# 16_PWM_LEDs_Module.net
KiCad netlist of a schematic drawn in EAGLE
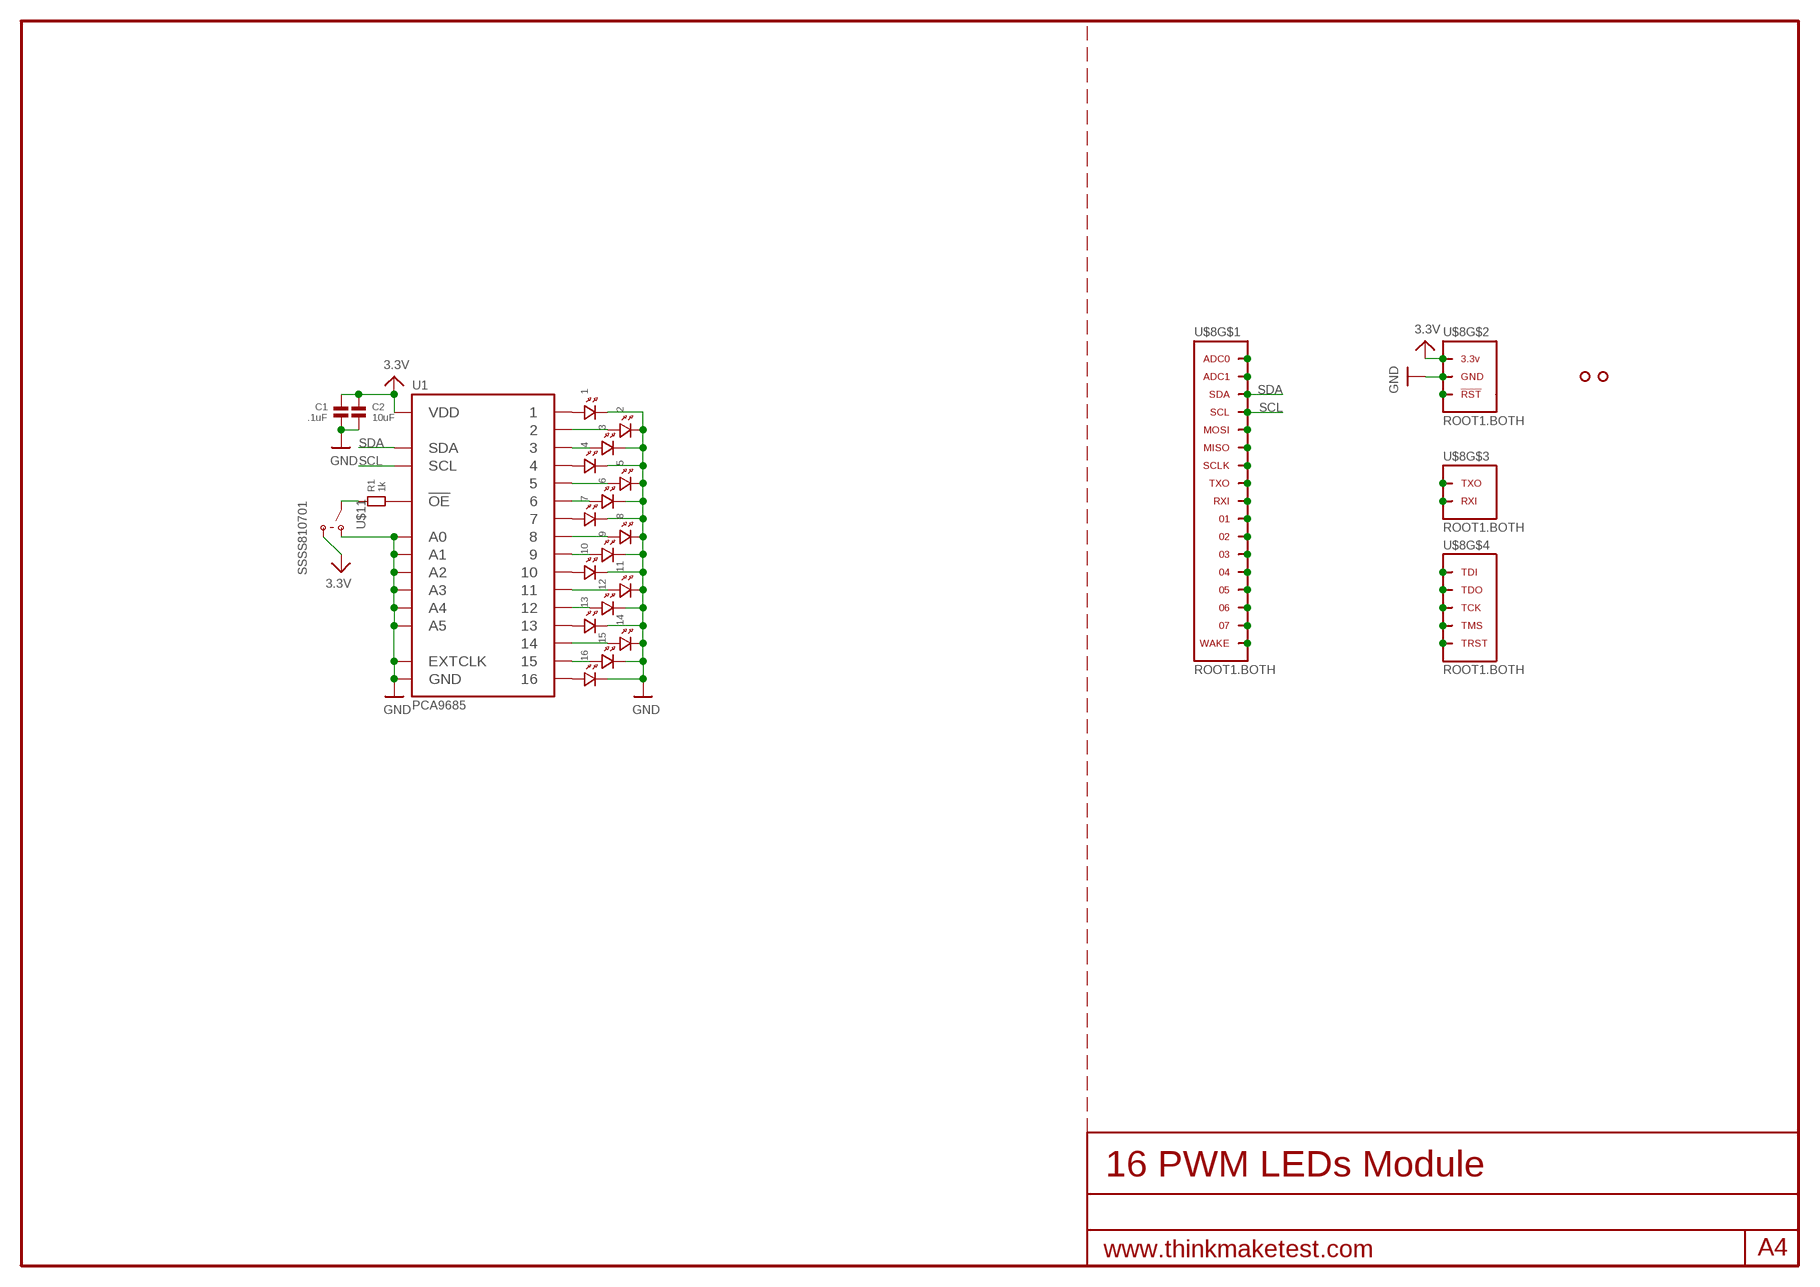
[diagram p0: schematic, sheet 1]

(export (version "E")
  (design (tool "Eeschema 10.0.6"))
  (components
    (comp (ref "1")
      (value "LED.0603")
      (footprint "eagle-import:0603.LED")
      (libsource (lib "eagle-import") (part "LED.0603"))
    )
    (comp (ref "2")
      (value "LED.0603")
      (footprint "eagle-import:0603.LED")
      (libsource (lib "eagle-import") (part "LED.0603"))
    )
    (comp (ref "3")
      (value "LED.0603")
      (footprint "eagle-import:0603.LED")
      (libsource (lib "eagle-import") (part "LED.0603"))
    )
    (comp (ref "4")
      (value "LED.0603")
      (footprint "eagle-import:0603.LED")
      (libsource (lib "eagle-import") (part "LED.0603"))
    )
    (comp (ref "5")
      (value "LED.0603")
      (footprint "eagle-import:0603.LED")
      (libsource (lib "eagle-import") (part "LED.0603"))
    )
    (comp (ref "6")
      (value "LED.0603")
      (footprint "eagle-import:0603.LED")
      (libsource (lib "eagle-import") (part "LED.0603"))
    )
    (comp (ref "7")
      (value "LED.0603")
      (footprint "eagle-import:0603.LED")
      (libsource (lib "eagle-import") (part "LED.0603"))
    )
    (comp (ref "8")
      (value "LED.0603")
      (footprint "eagle-import:0603.LED")
      (libsource (lib "eagle-import") (part "LED.0603"))
    )
    (comp (ref "9")
      (value "LED.0603")
      (footprint "eagle-import:0603.LED")
      (libsource (lib "eagle-import") (part "LED.0603"))
    )
    (comp (ref "10")
      (value "LED.0603")
      (footprint "eagle-import:0603.LED")
      (libsource (lib "eagle-import") (part "LED.0603"))
    )
    (comp (ref "11")
      (value "LED.0603")
      (footprint "eagle-import:0603.LED")
      (libsource (lib "eagle-import") (part "LED.0603"))
    )
    (comp (ref "12")
      (value "LED.0603")
      (footprint "eagle-import:0603.LED")
      (libsource (lib "eagle-import") (part "LED.0603"))
    )
    (comp (ref "13")
      (value "LED.0603")
      (footprint "eagle-import:0603.LED")
      (libsource (lib "eagle-import") (part "LED.0603"))
    )
    (comp (ref "14")
      (value "LED.0603")
      (footprint "eagle-import:0603.LED")
      (libsource (lib "eagle-import") (part "LED.0603"))
    )
    (comp (ref "15")
      (value "LED.0603")
      (footprint "eagle-import:0603.LED")
      (libsource (lib "eagle-import") (part "LED.0603"))
    )
    (comp (ref "16")
      (value "LED.0603")
      (footprint "eagle-import:0603.LED")
      (libsource (lib "eagle-import") (part "LED.0603"))
    )
    (comp (ref "C1")
      (value ".1uF")
      (footprint "eagle-import:0603")
      (libsource (lib "eagle-import") (part "CAPACITOR.0603"))
    )
    (comp (ref "C2")
      (value "10uF")
      (footprint "eagle-import:0805")
      (libsource (lib "eagle-import") (part "CAPACITOR.0805"))
    )
    (comp (ref "R1")
      (value "1k")
      (footprint "eagle-import:0603")
      (libsource (lib "eagle-import") (part "RESISTOR.0603"))
    )
    (comp (ref "U$3")
      (value "HOLE.2MM")
      (footprint "eagle-import:2MM")
      (libsource (lib "eagle-import") (part "HOLE.2MM"))
    )
    (comp (ref "U$4")
      (value "HOLE.2MM")
      (footprint "eagle-import:2MM")
      (libsource (lib "eagle-import") (part "HOLE.2MM"))
    )
    (comp (ref "U$8")
      (value "ROOT1.BOTH")
      (footprint "eagle-import:ROOT1.BOTH")
      (libsource (lib "eagle-import") (part "ROOT1.BOTH"))
    )
    (comp (ref "U$11")
      (value "SSSS810701")
      (footprint "eagle-import:SSSS810701")
      (libsource (lib "eagle-import") (part "SSSS810701"))
    )
    (comp (ref "U1")
      (value "PCA9685")
      (footprint "eagle-import:HVQFN28")
      (libsource (lib "eagle-import") (part "PCA9685"))
    )
  )
  (nets
    (net (code "1") (name "/SCL") (class "Default")
      (node (ref "U$8") (pin "SCL") (pinfunction "SCL_SCL") (pintype "bidirectional"))
      (node (ref "U$8") (pin "SCL@1") (pinfunction "SCL_SCL@1") (pintype "bidirectional"))
      (node (ref "U$8") (pin "SCL@VIA") (pinfunction "SCL_SCL@VIA") (pintype "bidirectional"))
      (node (ref "U1") (pin "26") (pinfunction "SCL_26") (pintype "bidirectional"))
    )
    (net (code "2") (name "/SDA") (class "Default")
      (node (ref "U$8") (pin "SDA") (pinfunction "SDA_SDA") (pintype "bidirectional"))
      (node (ref "U$8") (pin "SDA@1") (pinfunction "SDA_SDA@1") (pintype "bidirectional"))
      (node (ref "U$8") (pin "SDA@VIA") (pinfunction "SDA_SDA@VIA") (pintype "bidirectional"))
      (node (ref "U1") (pin "27") (pinfunction "SDA_27") (pintype "bidirectional"))
    )
    (net (code "3") (name "3.3V") (class "Default")
      (node (ref "C1") (pin "1") (pinfunction "1_1") (pintype "bidirectional"))
      (node (ref "C2") (pin "1") (pinfunction "1_1") (pintype "bidirectional"))
      (node (ref "U$11") (pin "1") (pinfunction "B_1") (pintype "bidirectional"))
      (node (ref "U$8") (pin "3.3V@1") (pinfunction "3.3V_3.3V@1") (pintype "bidirectional"))
      (node (ref "U$8") (pin "3.3V@10") (pinfunction "3.3V_3.3V@10") (pintype "bidirectional"))
      (node (ref "U$8") (pin "3.3V@11") (pinfunction "3.3V_3.3V@11") (pintype "bidirectional"))
      (node (ref "U$8") (pin "3.3V@12") (pinfunction "3.3V_3.3V@12") (pintype "bidirectional"))
      (node (ref "U$8") (pin "3.3V@13") (pinfunction "3.3V_3.3V@13") (pintype "bidirectional"))
      (node (ref "U$8") (pin "3.3V@14") (pinfunction "3.3V_3.3V@14") (pintype "bidirectional"))
      (node (ref "U$8") (pin "3.3V@15") (pinfunction "3.3V_3.3V@15") (pintype "bidirectional"))
      (node (ref "U$8") (pin "3.3V@16") (pinfunction "3.3V_3.3V@16") (pintype "bidirectional"))
      (node (ref "U$8") (pin "3.3V@17") (pinfunction "3.3V_3.3V@17") (pintype "bidirectional"))
      (node (ref "U$8") (pin "3.3V@18") (pinfunction "3.3V_3.3V@18") (pintype "bidirectional"))
      (node (ref "U$8") (pin "3.3V@19") (pinfunction "3.3V_3.3V@19") (pintype "bidirectional"))
      (node (ref "U$8") (pin "3.3V@2") (pinfunction "3.3V_3.3V@2") (pintype "bidirectional"))
      (node (ref "U$8") (pin "3.3V@20") (pinfunction "3.3V_3.3V@20") (pintype "bidirectional"))
      (node (ref "U$8") (pin "3.3V@21") (pinfunction "3.3V_3.3V@21") (pintype "bidirectional"))
      (node (ref "U$8") (pin "3.3V@22") (pinfunction "3.3V_3.3V@22") (pintype "bidirectional"))
      (node (ref "U$8") (pin "3.3V@23") (pinfunction "3.3V_3.3V@23") (pintype "bidirectional"))
      (node (ref "U$8") (pin "3.3V@24") (pinfunction "3.3V_3.3V@24") (pintype "bidirectional"))
      (node (ref "U$8") (pin "3.3V@3") (pinfunction "3.3V_3.3V@3") (pintype "bidirectional"))
      (node (ref "U$8") (pin "3.3V@4") (pinfunction "3.3V_3.3V@4") (pintype "bidirectional"))
      (node (ref "U$8") (pin "3.3V@5") (pinfunction "3.3V_3.3V@5") (pintype "bidirectional"))
      (node (ref "U$8") (pin "3.3V@6") (pinfunction "3.3V_3.3V@6") (pintype "bidirectional"))
      (node (ref "U$8") (pin "3.3V@7") (pinfunction "3.3V_3.3V@7") (pintype "bidirectional"))
      (node (ref "U$8") (pin "3.3V@8") (pinfunction "3.3V_3.3V@8") (pintype "bidirectional"))
      (node (ref "U$8") (pin "3.3V@9") (pinfunction "3.3V_3.3V@9") (pintype "bidirectional"))
      (node (ref "U$8") (pin "3.3V@VIA") (pinfunction "3.3V_3.3V@VIA") (pintype "bidirectional"))
      (node (ref "U1") (pin "28") (pinfunction "VDD_28") (pintype "bidirectional"))
    )
    (net (code "4") (name "GND") (class "Default")
      (node (ref "1") (pin "P$2") (pinfunction "2_P$2") (pintype "bidirectional"))
      (node (ref "10") (pin "P$2") (pinfunction "2_P$2") (pintype "bidirectional"))
      (node (ref "11") (pin "P$2") (pinfunction "2_P$2") (pintype "bidirectional"))
      (node (ref "12") (pin "P$2") (pinfunction "2_P$2") (pintype "bidirectional"))
      (node (ref "13") (pin "P$2") (pinfunction "2_P$2") (pintype "bidirectional"))
      (node (ref "14") (pin "P$2") (pinfunction "2_P$2") (pintype "bidirectional"))
      (node (ref "15") (pin "P$2") (pinfunction "2_P$2") (pintype "bidirectional"))
      (node (ref "16") (pin "P$2") (pinfunction "2_P$2") (pintype "bidirectional"))
      (node (ref "2") (pin "P$2") (pinfunction "2_P$2") (pintype "bidirectional"))
      (node (ref "3") (pin "P$2") (pinfunction "2_P$2") (pintype "bidirectional"))
      (node (ref "4") (pin "P$2") (pinfunction "2_P$2") (pintype "bidirectional"))
      (node (ref "5") (pin "P$2") (pinfunction "2_P$2") (pintype "bidirectional"))
      (node (ref "6") (pin "P$2") (pinfunction "2_P$2") (pintype "bidirectional"))
      (node (ref "7") (pin "P$2") (pinfunction "2_P$2") (pintype "bidirectional"))
      (node (ref "8") (pin "P$2") (pinfunction "2_P$2") (pintype "bidirectional"))
      (node (ref "9") (pin "P$2") (pinfunction "2_P$2") (pintype "bidirectional"))
      (node (ref "C1") (pin "2") (pinfunction "2_2") (pintype "bidirectional"))
      (node (ref "C2") (pin "2") (pinfunction "2_2") (pintype "bidirectional"))
      (node (ref "U$11") (pin "3") (pinfunction "A_3") (pintype "bidirectional"))
      (node (ref "U$8") (pin "GND@1") (pinfunction "GND_GND@1") (pintype "bidirectional"))
      (node (ref "U$8") (pin "GND@10") (pinfunction "GND_GND@10") (pintype "bidirectional"))
      (node (ref "U$8") (pin "GND@11") (pinfunction "GND_GND@11") (pintype "bidirectional"))
      (node (ref "U$8") (pin "GND@12") (pinfunction "GND_GND@12") (pintype "bidirectional"))
      (node (ref "U$8") (pin "GND@13") (pinfunction "GND_GND@13") (pintype "bidirectional"))
      (node (ref "U$8") (pin "GND@14") (pinfunction "GND_GND@14") (pintype "bidirectional"))
      (node (ref "U$8") (pin "GND@15") (pinfunction "GND_GND@15") (pintype "bidirectional"))
      (node (ref "U$8") (pin "GND@16") (pinfunction "GND_GND@16") (pintype "bidirectional"))
      (node (ref "U$8") (pin "GND@17") (pinfunction "GND_GND@17") (pintype "bidirectional"))
      (node (ref "U$8") (pin "GND@18") (pinfunction "GND_GND@18") (pintype "bidirectional"))
      (node (ref "U$8") (pin "GND@19") (pinfunction "GND_GND@19") (pintype "bidirectional"))
      (node (ref "U$8") (pin "GND@2") (pinfunction "GND_GND@2") (pintype "bidirectional"))
      (node (ref "U$8") (pin "GND@20") (pinfunction "GND_GND@20") (pintype "bidirectional"))
      (node (ref "U$8") (pin "GND@21") (pinfunction "GND_GND@21") (pintype "bidirectional"))
      (node (ref "U$8") (pin "GND@22") (pinfunction "GND_GND@22") (pintype "bidirectional"))
      (node (ref "U$8") (pin "GND@23") (pinfunction "GND_GND@23") (pintype "bidirectional"))
      (node (ref "U$8") (pin "GND@24") (pinfunction "GND_GND@24") (pintype "bidirectional"))
      (node (ref "U$8") (pin "GND@25") (pinfunction "GND_GND@25") (pintype "bidirectional"))
      (node (ref "U$8") (pin "GND@26") (pinfunction "GND_GND@26") (pintype "bidirectional"))
      (node (ref "U$8") (pin "GND@3") (pinfunction "GND_GND@3") (pintype "bidirectional"))
      (node (ref "U$8") (pin "GND@4") (pinfunction "GND_GND@4") (pintype "bidirectional"))
      (node (ref "U$8") (pin "GND@5") (pinfunction "GND_GND@5") (pintype "bidirectional"))
      (node (ref "U$8") (pin "GND@6") (pinfunction "GND_GND@6") (pintype "bidirectional"))
      (node (ref "U$8") (pin "GND@7") (pinfunction "GND_GND@7") (pintype "bidirectional"))
      (node (ref "U$8") (pin "GND@8") (pinfunction "GND_GND@8") (pintype "bidirectional"))
      (node (ref "U$8") (pin "GND@9") (pinfunction "GND_GND@9") (pintype "bidirectional"))
      (node (ref "U$8") (pin "GND@VIA") (pinfunction "GND_GND@VIA") (pintype "bidirectional"))
      (node (ref "U1") (pin "1") (pinfunction "A0_1") (pintype "bidirectional"))
      (node (ref "U1") (pin "14") (pinfunction "GND_14") (pintype "bidirectional"))
      (node (ref "U1") (pin "2") (pinfunction "A1_2") (pintype "bidirectional"))
      (node (ref "U1") (pin "24") (pinfunction "A5_24") (pintype "bidirectional"))
      (node (ref "U1") (pin "25") (pinfunction "EXTCLK_25") (pintype "bidirectional"))
      (node (ref "U1") (pin "3") (pinfunction "A2_3") (pintype "bidirectional"))
      (node (ref "U1") (pin "4") (pinfunction "A3_4") (pintype "bidirectional"))
      (node (ref "U1") (pin "5") (pinfunction "A4_5") (pintype "bidirectional"))
      (node (ref "U1") (pin "PAD") (pinfunction "GND_PAD") (pintype "bidirectional"))
    )
    (net (code "5") (name "Net-(1-1)") (class "Default")
      (node (ref "1") (pin "P$1") (pinfunction "1_P$1") (pintype "bidirectional"))
      (node (ref "U1") (pin "6") (pinfunction "1_6") (pintype "bidirectional"))
    )
    (net (code "6") (name "Net-(2-1)") (class "Default")
      (node (ref "2") (pin "P$1") (pinfunction "1_P$1") (pintype "bidirectional"))
      (node (ref "U1") (pin "7") (pinfunction "2_7") (pintype "bidirectional"))
    )
    (net (code "7") (name "Net-(3-1)") (class "Default")
      (node (ref "3") (pin "P$1") (pinfunction "1_P$1") (pintype "bidirectional"))
      (node (ref "U1") (pin "8") (pinfunction "3_8") (pintype "bidirectional"))
    )
    (net (code "8") (name "Net-(4-1)") (class "Default")
      (node (ref "4") (pin "P$1") (pinfunction "1_P$1") (pintype "bidirectional"))
      (node (ref "U1") (pin "9") (pinfunction "4_9") (pintype "bidirectional"))
    )
    (net (code "9") (name "Net-(5-1)") (class "Default")
      (node (ref "5") (pin "P$1") (pinfunction "1_P$1") (pintype "bidirectional"))
      (node (ref "U1") (pin "10") (pinfunction "5_10") (pintype "bidirectional"))
    )
    (net (code "10") (name "Net-(6-1)") (class "Default")
      (node (ref "6") (pin "P$1") (pinfunction "1_P$1") (pintype "bidirectional"))
      (node (ref "U1") (pin "11") (pinfunction "6_11") (pintype "bidirectional"))
    )
    (net (code "11") (name "Net-(7-1)") (class "Default")
      (node (ref "7") (pin "P$1") (pinfunction "1_P$1") (pintype "bidirectional"))
      (node (ref "U1") (pin "12") (pinfunction "7_12") (pintype "bidirectional"))
    )
    (net (code "12") (name "Net-(8-1)") (class "Default")
      (node (ref "8") (pin "P$1") (pinfunction "1_P$1") (pintype "bidirectional"))
      (node (ref "U1") (pin "13") (pinfunction "8_13") (pintype "bidirectional"))
    )
    (net (code "13") (name "Net-(9-1)") (class "Default")
      (node (ref "9") (pin "P$1") (pinfunction "1_P$1") (pintype "bidirectional"))
      (node (ref "U1") (pin "15") (pinfunction "9_15") (pintype "bidirectional"))
    )
    (net (code "14") (name "Net-(10-1)") (class "Default")
      (node (ref "10") (pin "P$1") (pinfunction "1_P$1") (pintype "bidirectional"))
      (node (ref "U1") (pin "16") (pinfunction "10_16") (pintype "bidirectional"))
    )
    (net (code "15") (name "Net-(11-1)") (class "Default")
      (node (ref "11") (pin "P$1") (pinfunction "1_P$1") (pintype "bidirectional"))
      (node (ref "U1") (pin "17") (pinfunction "11_17") (pintype "bidirectional"))
    )
    (net (code "16") (name "Net-(12-1)") (class "Default")
      (node (ref "12") (pin "P$1") (pinfunction "1_P$1") (pintype "bidirectional"))
      (node (ref "U1") (pin "18") (pinfunction "12_18") (pintype "bidirectional"))
    )
    (net (code "17") (name "Net-(13-1)") (class "Default")
      (node (ref "13") (pin "P$1") (pinfunction "1_P$1") (pintype "bidirectional"))
      (node (ref "U1") (pin "19") (pinfunction "13_19") (pintype "bidirectional"))
    )
    (net (code "18") (name "Net-(14-1)") (class "Default")
      (node (ref "14") (pin "P$1") (pinfunction "1_P$1") (pintype "bidirectional"))
      (node (ref "U1") (pin "20") (pinfunction "14_20") (pintype "bidirectional"))
    )
    (net (code "19") (name "Net-(15-1)") (class "Default")
      (node (ref "15") (pin "P$1") (pinfunction "1_P$1") (pintype "bidirectional"))
      (node (ref "U1") (pin "21") (pinfunction "15_21") (pintype "bidirectional"))
    )
    (net (code "20") (name "Net-(16-1)") (class "Default")
      (node (ref "16") (pin "P$1") (pinfunction "1_P$1") (pintype "bidirectional"))
      (node (ref "U1") (pin "22") (pinfunction "16_22") (pintype "bidirectional"))
    )
    (net (code "21") (name "Net-(U$8-Pad01)") (class "Default")
      (node (ref "U$8") (pin "01") (pinfunction "01_01") (pintype "bidirectional"))
      (node (ref "U$8") (pin "01@1") (pinfunction "01_01@1") (pintype "bidirectional"))
      (node (ref "U$8") (pin "01@VIA") (pinfunction "01_01@VIA") (pintype "bidirectional"))
    )
    (net (code "22") (name "Net-(U$8-Pad02)") (class "Default")
      (node (ref "U$8") (pin "02") (pinfunction "02_02") (pintype "bidirectional"))
      (node (ref "U$8") (pin "02@1") (pinfunction "02_02@1") (pintype "bidirectional"))
      (node (ref "U$8") (pin "02@VIA") (pinfunction "02_02@VIA") (pintype "bidirectional"))
    )
    (net (code "23") (name "Net-(U$8-Pad03)") (class "Default")
      (node (ref "U$8") (pin "03") (pinfunction "03_03") (pintype "bidirectional"))
      (node (ref "U$8") (pin "03@1") (pinfunction "03_03@1") (pintype "bidirectional"))
      (node (ref "U$8") (pin "03@VIA") (pinfunction "03_03@VIA") (pintype "bidirectional"))
    )
    (net (code "24") (name "Net-(U$8-Pad04)") (class "Default")
      (node (ref "U$8") (pin "04") (pinfunction "04_04") (pintype "bidirectional"))
      (node (ref "U$8") (pin "04@1") (pinfunction "04_04@1") (pintype "bidirectional"))
      (node (ref "U$8") (pin "04@VIA") (pinfunction "04_04@VIA") (pintype "bidirectional"))
    )
    (net (code "25") (name "Net-(U$8-Pad05)") (class "Default")
      (node (ref "U$8") (pin "05") (pinfunction "05_05") (pintype "bidirectional"))
      (node (ref "U$8") (pin "05@1") (pinfunction "05_05@1") (pintype "bidirectional"))
      (node (ref "U$8") (pin "05@VIA") (pinfunction "05_05@VIA") (pintype "bidirectional"))
    )
    (net (code "26") (name "Net-(U$8-Pad06)") (class "Default")
      (node (ref "U$8") (pin "06") (pinfunction "06_06") (pintype "bidirectional"))
      (node (ref "U$8") (pin "06@1") (pinfunction "06_06@1") (pintype "bidirectional"))
      (node (ref "U$8") (pin "06@VIA") (pinfunction "06_06@VIA") (pintype "bidirectional"))
    )
    (net (code "27") (name "Net-(U$8-Pad07)") (class "Default")
      (node (ref "U$8") (pin "07") (pinfunction "07_07") (pintype "bidirectional"))
      (node (ref "U$8") (pin "07@1") (pinfunction "07_07@1") (pintype "bidirectional"))
      (node (ref "U$8") (pin "07@VIA") (pinfunction "07_07@VIA") (pintype "bidirectional"))
    )
    (net (code "28") (name "Net-(U$8-PadADC0)") (class "Default")
      (node (ref "U$8") (pin "ADC0") (pinfunction "ADC0_ADC0") (pintype "bidirectional"))
      (node (ref "U$8") (pin "ADC0@1") (pinfunction "ADC0_ADC0@1") (pintype "bidirectional"))
      (node (ref "U$8") (pin "ADC0@VIA") (pinfunction "ADC0_ADC0@VIA") (pintype "bidirectional"))
    )
    (net (code "29") (name "Net-(U$8-PadADC1)") (class "Default")
      (node (ref "U$8") (pin "ADC1") (pinfunction "ADC1_ADC1") (pintype "bidirectional"))
      (node (ref "U$8") (pin "ADC1@1") (pinfunction "ADC1_ADC1@1") (pintype "bidirectional"))
      (node (ref "U$8") (pin "ADC1@VIA") (pinfunction "ADC1_ADC1@VIA") (pintype "bidirectional"))
    )
    (net (code "30") (name "Net-(U$8-PadMISO)") (class "Default")
      (node (ref "U$8") (pin "MISO") (pinfunction "MISO_MISO") (pintype "bidirectional"))
      (node (ref "U$8") (pin "MISO@1") (pinfunction "MISO_MISO@1") (pintype "bidirectional"))
      (node (ref "U$8") (pin "MISO@VIA") (pinfunction "MISO_MISO@VIA") (pintype "bidirectional"))
    )
    (net (code "31") (name "Net-(U$8-PadMOSI)") (class "Default")
      (node (ref "U$8") (pin "MOSI") (pinfunction "MOSI_MOSI") (pintype "bidirectional"))
      (node (ref "U$8") (pin "MOSI@1") (pinfunction "MOSI_MOSI@1") (pintype "bidirectional"))
      (node (ref "U$8") (pin "MOSI@VIA") (pinfunction "MOSI_MOSI@VIA") (pintype "bidirectional"))
    )
    (net (code "32") (name "Net-(U$8-PadRXI)") (class "Default")
      (node (ref "U$8") (pin "RXI") (pinfunction "RXI_RXI") (pintype "bidirectional"))
      (node (ref "U$8") (pin "RXI@1") (pinfunction "RXI_RXI@1") (pintype "bidirectional"))
      (node (ref "U$8") (pin "RXI@VIA") (pinfunction "RXI_RXI@VIA") (pintype "bidirectional"))
    )
    (net (code "33") (name "Net-(U$8-PadSCLK)") (class "Default")
      (node (ref "U$8") (pin "SCLK") (pinfunction "SCLK_SCLK") (pintype "bidirectional"))
      (node (ref "U$8") (pin "SCLK@1") (pinfunction "SCLK_SCLK@1") (pintype "bidirectional"))
      (node (ref "U$8") (pin "SCLK@VIA") (pinfunction "SCLK_SCLK@VIA") (pintype "bidirectional"))
    )
    (net (code "34") (name "Net-(U$8-PadTCK)") (class "Default")
      (node (ref "U$8") (pin "TCK") (pinfunction "TCK_TCK") (pintype "bidirectional"))
      (node (ref "U$8") (pin "TCK@1") (pinfunction "TCK_TCK@1") (pintype "bidirectional"))
      (node (ref "U$8") (pin "TCK@VIA") (pinfunction "TCK_TCK@VIA") (pintype "bidirectional"))
    )
    (net (code "35") (name "Net-(U$8-PadTDI)") (class "Default")
      (node (ref "U$8") (pin "TDI") (pinfunction "TDI_TDI") (pintype "bidirectional"))
      (node (ref "U$8") (pin "TDI@1") (pinfunction "TDI_TDI@1") (pintype "bidirectional"))
      (node (ref "U$8") (pin "TDI@VIA") (pinfunction "TDI_TDI@VIA") (pintype "bidirectional"))
    )
    (net (code "36") (name "Net-(U$8-PadTDO)") (class "Default")
      (node (ref "U$8") (pin "TDO") (pinfunction "TDO_TDO") (pintype "bidirectional"))
      (node (ref "U$8") (pin "TDO@1") (pinfunction "TDO_TDO@1") (pintype "bidirectional"))
      (node (ref "U$8") (pin "TDO@VIA") (pinfunction "TDO_TDO@VIA") (pintype "bidirectional"))
    )
    (net (code "37") (name "Net-(U$8-PadTMS)") (class "Default")
      (node (ref "U$8") (pin "TMS") (pinfunction "TMS_TMS") (pintype "bidirectional"))
      (node (ref "U$8") (pin "TMS@1") (pinfunction "TMS_TMS@1") (pintype "bidirectional"))
      (node (ref "U$8") (pin "TMS@VIA") (pinfunction "TMS_TMS@VIA") (pintype "bidirectional"))
    )
    (net (code "38") (name "Net-(U$8-PadTRST)") (class "Default")
      (node (ref "U$8") (pin "TRST") (pinfunction "TRST_TRST") (pintype "bidirectional"))
      (node (ref "U$8") (pin "TRST@1") (pinfunction "TRST_TRST@1") (pintype "bidirectional"))
      (node (ref "U$8") (pin "TRST@VIA") (pinfunction "TRST_TRST@VIA") (pintype "bidirectional"))
    )
    (net (code "39") (name "Net-(U$8-PadTXO)") (class "Default")
      (node (ref "U$8") (pin "TXO") (pinfunction "TXO_TXO") (pintype "bidirectional"))
      (node (ref "U$8") (pin "TXO@1") (pinfunction "TXO_TXO@1") (pintype "bidirectional"))
      (node (ref "U$8") (pin "TXO@VIA") (pinfunction "TXO_TXO@VIA") (pintype "bidirectional"))
    )
    (net (code "40") (name "Net-(U$8-PadWAKE)") (class "Default")
      (node (ref "U$8") (pin "WAKE") (pinfunction "WAKE_WAKE") (pintype "bidirectional"))
      (node (ref "U$8") (pin "WAKE@1") (pinfunction "WAKE_WAKE@1") (pintype "bidirectional"))
      (node (ref "U$8") (pin "WAKE@VIA") (pinfunction "WAKE_WAKE@VIA") (pintype "bidirectional"))
    )
    (net (code "41") (name "Net-(U$8B-~{RST}-PadRST)") (class "Default")
      (node (ref "U$8") (pin "RST") (pinfunction "~{RST}_RST") (pintype "bidirectional"))
      (node (ref "U$8") (pin "RST@1") (pinfunction "~{RST}_RST@1") (pintype "bidirectional"))
      (node (ref "U$8") (pin "RST@VIA") (pinfunction "~{RST}_RST@VIA") (pintype "bidirectional"))
    )
    (net (code "42") (name "Net-(U$8C-RXI-PadRXI.DBG)") (class "Default")
      (node (ref "U$8") (pin "RXI.DBG") (pinfunction "RXI_RXI.DBG") (pintype "bidirectional"))
      (node (ref "U$8") (pin "RXI.DBG@1") (pinfunction "RXI_RXI.DBG@1") (pintype "bidirectional"))
      (node (ref "U$8") (pin "RXI.DBG@VIA") (pinfunction "RXI_RXI.DBG@VIA") (pintype "bidirectional"))
    )
    (net (code "43") (name "Net-(U$8C-TXO-PadTXO.DBG)") (class "Default")
      (node (ref "U$8") (pin "TXO.DBG") (pinfunction "TXO_TXO.DBG") (pintype "bidirectional"))
      (node (ref "U$8") (pin "TXO.DBG@1") (pinfunction "TXO_TXO.DBG@1") (pintype "bidirectional"))
      (node (ref "U$8") (pin "TXO.DBG@VIA") (pinfunction "TXO_TXO.DBG@VIA") (pintype "bidirectional"))
    )
    (net (code "44") (name "Net-(U$11-COM)") (class "Default")
      (node (ref "R1") (pin "1") (pinfunction "1_1") (pintype "bidirectional"))
      (node (ref "U$11") (pin "2") (pinfunction "COM_2") (pintype "bidirectional"))
    )
    (net (code "45") (name "Net-(U1-~{OE})") (class "Default")
      (node (ref "R1") (pin "2") (pinfunction "2_2") (pintype "bidirectional"))
      (node (ref "U1") (pin "23") (pinfunction "~{OE}_23") (pintype "bidirectional"))
    )
  )
)
